# WiFiLedBoard.net
KiCad netlist of a schematic drawn in EAGLE
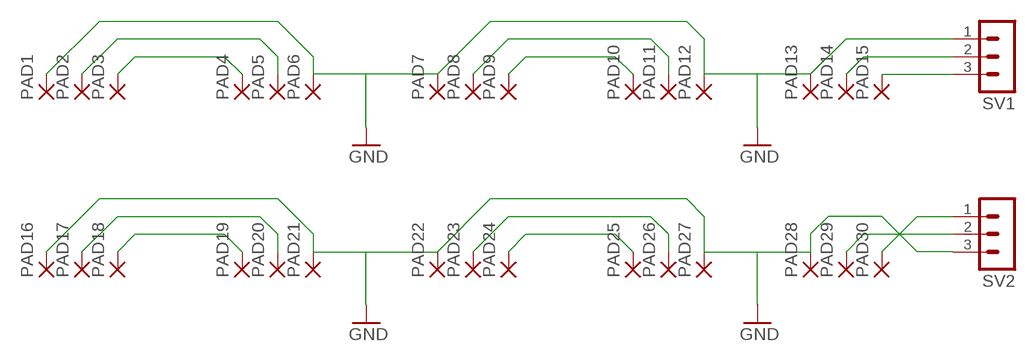
[diagram p0: schematic, sheet 1]

(export (version "E")
  (design (tool "Eeschema 10.0.6"))
  (components
    (comp (ref "PAD1")
      (value "SMD2")
      (footprint "eagle-import:SMD1,27-2,54")
      (libsource (lib "eagle-import") (part "SMD2"))
    )
    (comp (ref "PAD2")
      (value "SMD2")
      (footprint "eagle-import:SMD1,27-2,54")
      (libsource (lib "eagle-import") (part "SMD2"))
    )
    (comp (ref "PAD3")
      (value "SMD2")
      (footprint "eagle-import:SMD1,27-2,54")
      (libsource (lib "eagle-import") (part "SMD2"))
    )
    (comp (ref "PAD4")
      (value "SMD2")
      (footprint "eagle-import:SMD1,27-2,54")
      (libsource (lib "eagle-import") (part "SMD2"))
    )
    (comp (ref "PAD5")
      (value "SMD2")
      (footprint "eagle-import:SMD1,27-2,54")
      (libsource (lib "eagle-import") (part "SMD2"))
    )
    (comp (ref "PAD6")
      (value "SMD2")
      (footprint "eagle-import:SMD1,27-2,54")
      (libsource (lib "eagle-import") (part "SMD2"))
    )
    (comp (ref "PAD7")
      (value "SMD2")
      (footprint "eagle-import:SMD1,27-2,54")
      (libsource (lib "eagle-import") (part "SMD2"))
    )
    (comp (ref "PAD8")
      (value "SMD2")
      (footprint "eagle-import:SMD1,27-2,54")
      (libsource (lib "eagle-import") (part "SMD2"))
    )
    (comp (ref "PAD9")
      (value "SMD2")
      (footprint "eagle-import:SMD1,27-2,54")
      (libsource (lib "eagle-import") (part "SMD2"))
    )
    (comp (ref "PAD10")
      (value "SMD2")
      (footprint "eagle-import:SMD1,27-2,54")
      (libsource (lib "eagle-import") (part "SMD2"))
    )
    (comp (ref "PAD11")
      (value "SMD2")
      (footprint "eagle-import:SMD1,27-2,54")
      (libsource (lib "eagle-import") (part "SMD2"))
    )
    (comp (ref "PAD12")
      (value "SMD2")
      (footprint "eagle-import:SMD1,27-2,54")
      (libsource (lib "eagle-import") (part "SMD2"))
    )
    (comp (ref "PAD13")
      (value "SMD2")
      (footprint "eagle-import:SMD1,27-2,54")
      (libsource (lib "eagle-import") (part "SMD2"))
    )
    (comp (ref "PAD14")
      (value "SMD2")
      (footprint "eagle-import:SMD1,27-2,54")
      (libsource (lib "eagle-import") (part "SMD2"))
    )
    (comp (ref "PAD15")
      (value "SMD2")
      (footprint "eagle-import:SMD1,27-2,54")
      (libsource (lib "eagle-import") (part "SMD2"))
    )
    (comp (ref "PAD16")
      (value "SMD2")
      (footprint "eagle-import:SMD1,27-2,54")
      (libsource (lib "eagle-import") (part "SMD2"))
    )
    (comp (ref "PAD17")
      (value "SMD2")
      (footprint "eagle-import:SMD1,27-2,54")
      (libsource (lib "eagle-import") (part "SMD2"))
    )
    (comp (ref "PAD18")
      (value "SMD2")
      (footprint "eagle-import:SMD1,27-2,54")
      (libsource (lib "eagle-import") (part "SMD2"))
    )
    (comp (ref "PAD19")
      (value "SMD2")
      (footprint "eagle-import:SMD1,27-2,54")
      (libsource (lib "eagle-import") (part "SMD2"))
    )
    (comp (ref "PAD20")
      (value "SMD2")
      (footprint "eagle-import:SMD1,27-2,54")
      (libsource (lib "eagle-import") (part "SMD2"))
    )
    (comp (ref "PAD21")
      (value "SMD2")
      (footprint "eagle-import:SMD1,27-2,54")
      (libsource (lib "eagle-import") (part "SMD2"))
    )
    (comp (ref "PAD22")
      (value "SMD2")
      (footprint "eagle-import:SMD1,27-2,54")
      (libsource (lib "eagle-import") (part "SMD2"))
    )
    (comp (ref "PAD23")
      (value "SMD2")
      (footprint "eagle-import:SMD1,27-2,54")
      (libsource (lib "eagle-import") (part "SMD2"))
    )
    (comp (ref "PAD24")
      (value "SMD2")
      (footprint "eagle-import:SMD1,27-2,54")
      (libsource (lib "eagle-import") (part "SMD2"))
    )
    (comp (ref "PAD25")
      (value "SMD2")
      (footprint "eagle-import:SMD1,27-2,54")
      (libsource (lib "eagle-import") (part "SMD2"))
    )
    (comp (ref "PAD26")
      (value "SMD2")
      (footprint "eagle-import:SMD1,27-2,54")
      (libsource (lib "eagle-import") (part "SMD2"))
    )
    (comp (ref "PAD27")
      (value "SMD2")
      (footprint "eagle-import:SMD1,27-2,54")
      (libsource (lib "eagle-import") (part "SMD2"))
    )
    (comp (ref "PAD28")
      (value "SMD2")
      (footprint "eagle-import:SMD1,27-2,54")
      (libsource (lib "eagle-import") (part "SMD2"))
    )
    (comp (ref "PAD29")
      (value "SMD2")
      (footprint "eagle-import:SMD1,27-2,54")
      (libsource (lib "eagle-import") (part "SMD2"))
    )
    (comp (ref "PAD30")
      (value "SMD2")
      (footprint "eagle-import:SMD1,27-2,54")
      (libsource (lib "eagle-import") (part "SMD2"))
    )
    (comp (ref "SV1")
      (value "MA03-1")
      (footprint "eagle-import:MA03-1")
      (libsource (lib "eagle-import") (part "MA03-1"))
    )
    (comp (ref "SV2")
      (value "MA03-1")
      (footprint "eagle-import:MA03-1")
      (libsource (lib "eagle-import") (part "MA03-1"))
    )
  )
  (nets
    (net (code "1") (name "GND") (class "Default")
      (node (ref "PAD1") (pin "1") (pinfunction "P_1") (pintype "passive"))
      (node (ref "PAD12") (pin "1") (pinfunction "P_1") (pintype "passive"))
      (node (ref "PAD13") (pin "1") (pinfunction "P_1") (pintype "passive"))
      (node (ref "PAD16") (pin "1") (pinfunction "P_1") (pintype "passive"))
      (node (ref "PAD21") (pin "1") (pinfunction "P_1") (pintype "passive"))
      (node (ref "PAD22") (pin "1") (pinfunction "P_1") (pintype "passive"))
      (node (ref "PAD27") (pin "1") (pinfunction "P_1") (pintype "passive"))
      (node (ref "PAD28") (pin "1") (pinfunction "P_1") (pintype "passive"))
      (node (ref "PAD6") (pin "1") (pinfunction "P_1") (pintype "passive"))
      (node (ref "PAD7") (pin "1") (pinfunction "P_1") (pintype "passive"))
      (node (ref "SV1") (pin "1") (pinfunction "1_1") (pintype "passive"))
      (node (ref "SV2") (pin "3") (pinfunction "3_3") (pintype "passive"))
    )
    (net (code "2") (name "Net-(PAD2-P)") (class "Default")
      (node (ref "PAD2") (pin "1") (pinfunction "P_1") (pintype "passive"))
      (node (ref "PAD5") (pin "1") (pinfunction "P_1") (pintype "passive"))
    )
    (net (code "3") (name "Net-(PAD3-P)") (class "Default")
      (node (ref "PAD3") (pin "1") (pinfunction "P_1") (pintype "passive"))
      (node (ref "PAD4") (pin "1") (pinfunction "P_1") (pintype "passive"))
    )
    (net (code "4") (name "Net-(PAD10-P)") (class "Default")
      (node (ref "PAD10") (pin "1") (pinfunction "P_1") (pintype "passive"))
      (node (ref "PAD9") (pin "1") (pinfunction "P_1") (pintype "passive"))
    )
    (net (code "5") (name "Net-(PAD11-P)") (class "Default")
      (node (ref "PAD11") (pin "1") (pinfunction "P_1") (pintype "passive"))
      (node (ref "PAD8") (pin "1") (pinfunction "P_1") (pintype "passive"))
    )
    (net (code "6") (name "Net-(PAD14-P)") (class "Default")
      (node (ref "PAD14") (pin "1") (pinfunction "P_1") (pintype "passive"))
      (node (ref "SV1") (pin "2") (pinfunction "2_2") (pintype "passive"))
    )
    (net (code "7") (name "Net-(PAD15-P)") (class "Default")
      (node (ref "PAD15") (pin "1") (pinfunction "P_1") (pintype "passive"))
      (node (ref "SV1") (pin "3") (pinfunction "3_3") (pintype "passive"))
    )
    (net (code "8") (name "Net-(PAD17-P)") (class "Default")
      (node (ref "PAD17") (pin "1") (pinfunction "P_1") (pintype "passive"))
      (node (ref "PAD20") (pin "1") (pinfunction "P_1") (pintype "passive"))
    )
    (net (code "9") (name "Net-(PAD18-P)") (class "Default")
      (node (ref "PAD18") (pin "1") (pinfunction "P_1") (pintype "passive"))
      (node (ref "PAD19") (pin "1") (pinfunction "P_1") (pintype "passive"))
    )
    (net (code "10") (name "Net-(PAD23-P)") (class "Default")
      (node (ref "PAD23") (pin "1") (pinfunction "P_1") (pintype "passive"))
      (node (ref "PAD26") (pin "1") (pinfunction "P_1") (pintype "passive"))
    )
    (net (code "11") (name "Net-(PAD24-P)") (class "Default")
      (node (ref "PAD24") (pin "1") (pinfunction "P_1") (pintype "passive"))
      (node (ref "PAD25") (pin "1") (pinfunction "P_1") (pintype "passive"))
    )
    (net (code "12") (name "Net-(PAD29-P)") (class "Default")
      (node (ref "PAD29") (pin "1") (pinfunction "P_1") (pintype "passive"))
      (node (ref "SV2") (pin "2") (pinfunction "2_2") (pintype "passive"))
    )
    (net (code "13") (name "Net-(PAD30-P)") (class "Default")
      (node (ref "PAD30") (pin "1") (pinfunction "P_1") (pintype "passive"))
      (node (ref "SV2") (pin "1") (pinfunction "1_1") (pintype "passive"))
    )
  )
)
